# RTD_1k_Wheatstone_PGA-ADC.net
KiCad netlist of a schematic drawn in Altium Designer
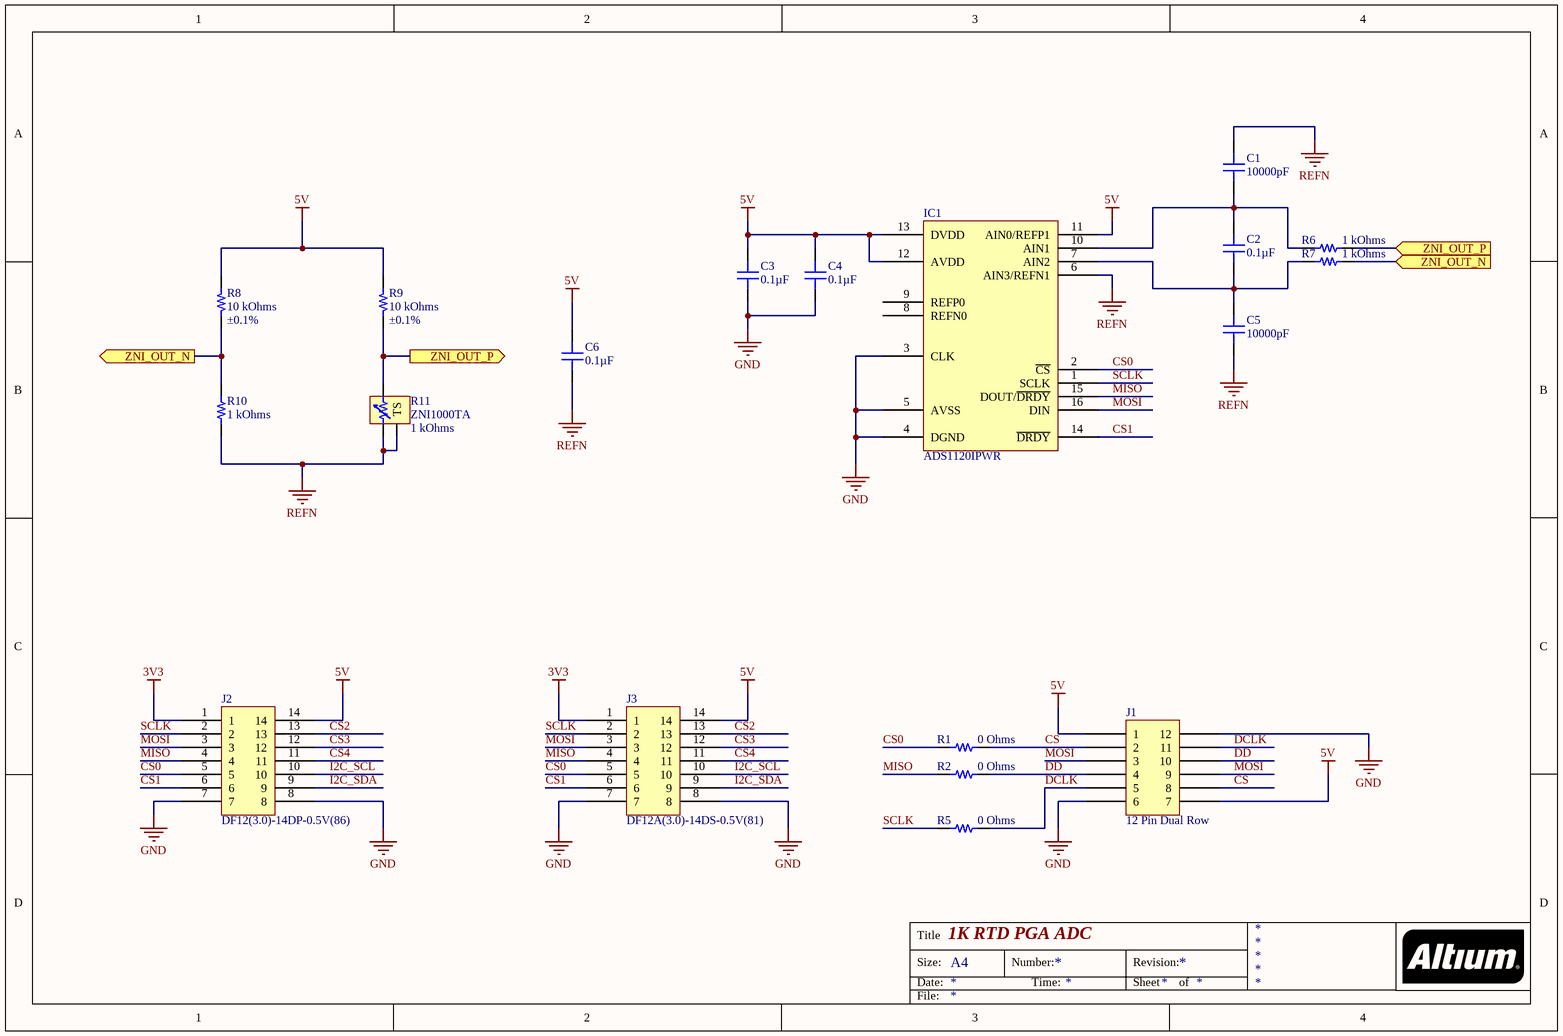
[diagram p0: RTD 1k Wheatstone PGA-ADC.SchDoc]

(export (version "E")
  (design (tool "Eeschema 10.0.6"))
  (components
    (comp (ref "C1")
      (value "10000pF")
      (footprint "CAP 0603_1608")
      (description "CAP CER 10000PF 50V X7R 0603")
      (fields (field (name "PART NUMBER") "AC0603KPX7R9BB103") (field (name "MANUFACTURER") "Yageo"))
      (libsource (lib "altiumlibrary.com") (part "Capacitor"))
    )
    (comp (ref "C2")
      (value "0.1µF")
      (footprint "CAP 0603_1608")
      (description "CAP CER 0.1UF 16V Y5V 0603")
      (fields (field (name "PART NUMBER") "CC0603ZRY5V7BB104") (field (name "MANUFACTURER") "Yageo"))
      (libsource (lib "altiumlibrary.com") (part "Capacitor"))
    )
    (comp (ref "C3")
      (value "0.1µF")
      (footprint "CAP 0603_1608")
      (description "CAP CER 0.1UF 16V Y5V 0603")
      (fields (field (name "PART NUMBER") "CC0603ZRY5V7BB104") (field (name "MANUFACTURER") "Yageo"))
      (libsource (lib "altiumlibrary.com") (part "Capacitor"))
    )
    (comp (ref "C4")
      (value "0.1µF")
      (footprint "CAP 0603_1608")
      (description "CAP CER 0.1UF 16V Y5V 0603")
      (fields (field (name "PART NUMBER") "CC0603ZRY5V7BB104") (field (name "MANUFACTURER") "Yageo"))
      (libsource (lib "altiumlibrary.com") (part "Capacitor"))
    )
    (comp (ref "C5")
      (value "10000pF")
      (footprint "CAP 0603_1608")
      (description "CAP CER 10000PF 50V X7R 0603")
      (fields (field (name "PART NUMBER") "AC0603KPX7R9BB103") (field (name "MANUFACTURER") "Yageo"))
      (libsource (lib "altiumlibrary.com") (part "Capacitor"))
    )
    (comp (ref "C6")
      (value "0.1µF")
      (footprint "CAP 0603_1608")
      (description "CAP CER 0.1UF 16V Y5V 0603")
      (fields (field (name "PART NUMBER") "CC0603ZRY5V7BB104") (field (name "MANUFACTURER") "Yageo"))
      (libsource (lib "altiumlibrary.com") (part "Capacitor"))
    )
    (comp (ref "IC1")
      (value "ADS1120IPWR")
      (footprint "TI TSSOP-16 PW")
      (description "IC ADC 16BIT SIGMA-DELTA 16TSSOP")
      (fields (field (name "MANUFACTURER") "Texas Instruments"))
      (libsource (lib "altiumlibrary.com") (part "TI ADS1120 TSSOP"))
    )
    (comp (ref "J1")
      (value "12 Pin Dual Row")
      (footprint "TE 5650118-3 Card Edge")
      (libsource (lib "CelestialUseful") (part "12 Pin Dual Row"))
    )
    (comp (ref "J2")
      (value "DF12(3.0)-14DP-0.5V(86)")
      (footprint "HIROSE DF12 3.0-14DP-0.5V 86")
      (description "CONN HDR 14POS SMD GOLD")
      (fields (field (name "MANUFACTURER") "Hirose Electric Co Ltd"))
      (libsource (lib "altiumlibrary.com") (part "14 Pin Dual Row"))
    )
    (comp (ref "J3")
      (value "DF12A(3.0)-14DS-0.5V(81)")
      (footprint "HIROSE DF12A 3.0-14DS-0.5V 81")
      (description "CONN RCPT 14POS SMD GOLD")
      (fields (field (name "MANUFACTURER") "Hirose Electric Co Ltd"))
      (libsource (lib "altiumlibrary.com") (part "14 Pin Dual Row"))
    )
    (comp (ref "R1")
      (value "0 Ohms")
      (footprint "RES 0603_1608")
      (description "RES SMD 0 OHM JUMPER 1/10W 0603")
      (fields
        (field (name "PART NUMBER") "ERJ-3GEY0R00V")
        (field (name "MANUFACTURER") "Panasonic Electronic Components")
      )
      (libsource (lib "altiumlibrary.com") (part "Resistor"))
    )
    (comp (ref "R2")
      (value "0 Ohms")
      (footprint "RES 0603_1608")
      (description "RES SMD 0 OHM JUMPER 1/10W 0603")
      (fields
        (field (name "PART NUMBER") "ERJ-3GEY0R00V")
        (field (name "MANUFACTURER") "Panasonic Electronic Components")
      )
      (libsource (lib "altiumlibrary.com") (part "Resistor"))
    )
    (comp (ref "R5")
      (value "0 Ohms")
      (footprint "RES 0603_1608")
      (description "RES SMD 0 OHM JUMPER 1/10W 0603")
      (fields
        (field (name "PART NUMBER") "ERJ-3GEY0R00V")
        (field (name "MANUFACTURER") "Panasonic Electronic Components")
      )
      (libsource (lib "altiumlibrary.com") (part "Resistor"))
    )
    (comp (ref "R6")
      (value "1 kOhms")
      (footprint "RES 0603_1608")
      (description "RES SMD 1K OHM 0.1% 1/5W 0603")
      (fields
        (field (name "PART NUMBER") "ERJ-PB3B1001V")
        (field (name "MANUFACTURER") "Panasonic Electronic Components")
      )
      (libsource (lib "altiumlibrary.com") (part "Resistor"))
    )
    (comp (ref "R7")
      (value "1 kOhms")
      (footprint "RES 0603_1608")
      (description "RES SMD 1K OHM 0.1% 1/5W 0603")
      (fields
        (field (name "PART NUMBER") "ERJ-PB3B1001V")
        (field (name "MANUFACTURER") "Panasonic Electronic Components")
      )
      (libsource (lib "altiumlibrary.com") (part "Resistor"))
    )
    (comp (ref "R8")
      (value "10 kOhms")
      (footprint "RES 0603_1608")
      (description "RES SMD 10K OHM 0.1% 1/10W 0603")
      (fields
        (field (name "PART NUMBER") "ERA-3AEB103V")
        (field (name "MANUFACTURER") "Panasonic Electronic Components")
        (field (name "TOLERANCE") "±0.1%")
      )
      (libsource (lib "altiumlibrary.com") (part "Resistor"))
    )
    (comp (ref "R9")
      (value "10 kOhms")
      (footprint "RES 0603_1608")
      (description "RES SMD 10K OHM 0.1% 1/10W 0603")
      (fields
        (field (name "PART NUMBER") "ERA-3AEB103V")
        (field (name "MANUFACTURER") "Panasonic Electronic Components")
        (field (name "TOLERANCE") "±0.1%")
      )
      (libsource (lib "altiumlibrary.com") (part "Resistor"))
    )
    (comp (ref "R10")
      (value "1 kOhms")
      (footprint "RES 0603_1608")
      (description "RES SMD 1K OHM 0.1% 1/5W 0603")
      (fields
        (field (name "PART NUMBER") "ERJ-PB3B1001V")
        (field (name "MANUFACTURER") "Panasonic Electronic Components")
      )
      (libsource (lib "altiumlibrary.com") (part "Resistor"))
    )
    (comp (ref "R11")
      (value "ZNI1000TA")
      (footprint "DIODES SOT-23-3")
      (description "SENSOR RTD 1KOHM 5% TO236-3")
      (fields (field (name "MANUFACTURER") "Diodes Incorporated") (field (name "RESISTANCE @ 0°C") "1 kOhms"))
      (libsource (lib "altiumlibrary.com") (part "DIODES INC ZNI1000"))
    )
  )
  (nets
    (net (code "1") (name "/CS") (class "Default")
      (node (ref "J1") (pin "2") (pinfunction "2_2") (pintype "passive"))
      (node (ref "J1") (pin "8") (pinfunction "8_8") (pintype "passive"))
      (node (ref "R1") (pin "2") (pinfunction "2_2") (pintype "passive"))
    )
    (net (code "2") (name "/CS0") (class "Default")
      (node (ref "IC1") (pin "2") (pinfunction "~{CS}_2") (pintype "passive"))
      (node (ref "J2") (pin "5") (pinfunction "5_5") (pintype "passive"))
      (node (ref "J3") (pin "5") (pinfunction "5_5") (pintype "passive"))
      (node (ref "R1") (pin "1") (pinfunction "1_1") (pintype "passive"))
    )
    (net (code "3") (name "/CS1") (class "Default")
      (node (ref "IC1") (pin "14") (pinfunction "~{DRDY}_14") (pintype "passive"))
      (node (ref "J2") (pin "6") (pinfunction "6_6") (pintype "passive"))
      (node (ref "J3") (pin "6") (pinfunction "6_6") (pintype "passive"))
    )
    (net (code "4") (name "/CS2") (class "Default")
      (node (ref "J2") (pin "13") (pinfunction "13_13") (pintype "passive"))
      (node (ref "J3") (pin "13") (pinfunction "13_13") (pintype "passive"))
    )
    (net (code "5") (name "/CS3") (class "Default")
      (node (ref "J2") (pin "12") (pinfunction "12_12") (pintype "passive"))
      (node (ref "J3") (pin "12") (pinfunction "12_12") (pintype "passive"))
    )
    (net (code "6") (name "/CS4") (class "Default")
      (node (ref "J2") (pin "11") (pinfunction "11_11") (pintype "passive"))
      (node (ref "J3") (pin "11") (pinfunction "11_11") (pintype "passive"))
    )
    (net (code "7") (name "/DCLK") (class "Default")
      (node (ref "J1") (pin "11") (pinfunction "11_11") (pintype "passive"))
      (node (ref "J1") (pin "5") (pinfunction "5_5") (pintype "passive"))
      (node (ref "R5") (pin "2") (pinfunction "2_2") (pintype "passive"))
    )
    (net (code "8") (name "/DD") (class "Default")
      (node (ref "J1") (pin "10") (pinfunction "10_10") (pintype "passive"))
      (node (ref "J1") (pin "4") (pinfunction "4_4") (pintype "passive"))
      (node (ref "R2") (pin "2") (pinfunction "2_2") (pintype "passive"))
    )
    (net (code "9") (name "/I2C_SCL") (class "Default")
      (node (ref "J2") (pin "10") (pinfunction "10_10") (pintype "passive"))
      (node (ref "J3") (pin "10") (pinfunction "10_10") (pintype "passive"))
    )
    (net (code "10") (name "/I2C_SDA") (class "Default")
      (node (ref "J2") (pin "9") (pinfunction "9_9") (pintype "passive"))
      (node (ref "J3") (pin "9") (pinfunction "9_9") (pintype "passive"))
    )
    (net (code "11") (name "/MISO") (class "Default")
      (node (ref "IC1") (pin "15") (pinfunction "DOUT/~{DRDY}_15") (pintype "passive"))
      (node (ref "J2") (pin "4") (pinfunction "4_4") (pintype "passive"))
      (node (ref "J3") (pin "4") (pinfunction "4_4") (pintype "passive"))
      (node (ref "R2") (pin "1") (pinfunction "1_1") (pintype "passive"))
    )
    (net (code "12") (name "/MOSI") (class "Default")
      (node (ref "IC1") (pin "16") (pinfunction "DIN_16") (pintype "passive"))
      (node (ref "J1") (pin "3") (pinfunction "3_3") (pintype "passive"))
      (node (ref "J1") (pin "9") (pinfunction "9_9") (pintype "passive"))
      (node (ref "J2") (pin "3") (pinfunction "3_3") (pintype "passive"))
      (node (ref "J3") (pin "3") (pinfunction "3_3") (pintype "passive"))
    )
    (net (code "13") (name "/SCLK") (class "Default")
      (node (ref "IC1") (pin "1") (pinfunction "SCLK_1") (pintype "passive"))
      (node (ref "J2") (pin "2") (pinfunction "2_2") (pintype "passive"))
      (node (ref "J3") (pin "2") (pinfunction "2_2") (pintype "passive"))
      (node (ref "R5") (pin "1") (pinfunction "1_1") (pintype "passive"))
    )
    (net (code "14") (name "/ZNI_OUT_N") (class "Default")
      (node (ref "R10") (pin "2") (pinfunction "2_2") (pintype "passive"))
      (node (ref "R7") (pin "1") (pinfunction "1_1") (pintype "passive"))
      (node (ref "R8") (pin "1") (pinfunction "1_1") (pintype "passive"))
    )
    (net (code "15") (name "/ZNI_OUT_P") (class "Default")
      (node (ref "R11") (pin "2") (pinfunction "2_2") (pintype "passive"))
      (node (ref "R6") (pin "1") (pinfunction "1_1") (pintype "passive"))
      (node (ref "R9") (pin "1") (pinfunction "1_1") (pintype "passive"))
    )
    (net (code "16") (name "3V3") (class "Default")
      (node (ref "J2") (pin "1") (pinfunction "1_1") (pintype "passive"))
      (node (ref "J3") (pin "1") (pinfunction "1_1") (pintype "passive"))
    )
    (net (code "17") (name "5V") (class "Default")
      (node (ref "C3") (pin "1") (pinfunction "1_1") (pintype "passive"))
      (node (ref "C4") (pin "1") (pinfunction "1_1") (pintype "passive"))
      (node (ref "C6") (pin "1") (pinfunction "1_1") (pintype "passive"))
      (node (ref "IC1") (pin "11") (pinfunction "AIN0/REFP1_11") (pintype "passive"))
      (node (ref "IC1") (pin "12") (pinfunction "AVDD_12") (pintype "passive"))
      (node (ref "IC1") (pin "13") (pinfunction "DVDD_13") (pintype "passive"))
      (node (ref "J1") (pin "1") (pinfunction "1_1") (pintype "passive"))
      (node (ref "J1") (pin "7") (pinfunction "7_7") (pintype "passive"))
      (node (ref "J2") (pin "14") (pinfunction "14_14") (pintype "passive"))
      (node (ref "J3") (pin "14") (pinfunction "14_14") (pintype "passive"))
      (node (ref "R8") (pin "2") (pinfunction "2_2") (pintype "passive"))
      (node (ref "R9") (pin "2") (pinfunction "2_2") (pintype "passive"))
    )
    (net (code "18") (name "GND") (class "Default")
      (node (ref "C3") (pin "2") (pinfunction "2_2") (pintype "passive"))
      (node (ref "C4") (pin "2") (pinfunction "2_2") (pintype "passive"))
      (node (ref "IC1") (pin "3") (pinfunction "CLK_3") (pintype "passive"))
      (node (ref "IC1") (pin "4") (pinfunction "DGND_4") (pintype "passive"))
      (node (ref "IC1") (pin "5") (pinfunction "AVSS_5") (pintype "passive"))
      (node (ref "J1") (pin "12") (pinfunction "12_12") (pintype "passive"))
      (node (ref "J1") (pin "6") (pinfunction "6_6") (pintype "passive"))
      (node (ref "J2") (pin "7") (pinfunction "7_7") (pintype "passive"))
      (node (ref "J2") (pin "8") (pinfunction "8_8") (pintype "passive"))
      (node (ref "J3") (pin "7") (pinfunction "7_7") (pintype "passive"))
      (node (ref "J3") (pin "8") (pinfunction "8_8") (pintype "passive"))
    )
    (net (code "19") (name "Net-(IC1-AIN1)") (class "Default")
      (node (ref "C1") (pin "1") (pinfunction "1_1") (pintype "passive"))
      (node (ref "C2") (pin "1") (pinfunction "1_1") (pintype "passive"))
      (node (ref "IC1") (pin "10") (pinfunction "AIN1_10") (pintype "passive"))
      (node (ref "R6") (pin "2") (pinfunction "2_2") (pintype "passive"))
    )
    (net (code "20") (name "Net-(IC1-AIN2)") (class "Default")
      (node (ref "C2") (pin "2") (pinfunction "2_2") (pintype "passive"))
      (node (ref "C5") (pin "2") (pinfunction "2_2") (pintype "passive"))
      (node (ref "IC1") (pin "7") (pinfunction "AIN2_7") (pintype "passive"))
      (node (ref "R7") (pin "2") (pinfunction "2_2") (pintype "passive"))
    )
    (net (code "21") (name "REFN") (class "Default")
      (node (ref "C1") (pin "2") (pinfunction "2_2") (pintype "passive"))
      (node (ref "C5") (pin "1") (pinfunction "1_1") (pintype "passive"))
      (node (ref "C6") (pin "2") (pinfunction "2_2") (pintype "passive"))
      (node (ref "IC1") (pin "6") (pinfunction "AIN3/REFN1_6") (pintype "passive"))
      (node (ref "R10") (pin "1") (pinfunction "1_1") (pintype "passive"))
      (node (ref "R11") (pin "1") (pinfunction "1_1") (pintype "passive"))
      (node (ref "R11") (pin "3") (pinfunction "TS_3") (pintype "passive"))
    )
    (net (code "22") (name "unconnected-(IC1-REFN0-Pad8)") (class "Default")
      (node (ref "IC1") (pin "8") (pinfunction "REFN0_8") (pintype "passive"))
    )
    (net (code "23") (name "unconnected-(IC1-REFP0-Pad9)") (class "Default")
      (node (ref "IC1") (pin "9") (pinfunction "REFP0_9") (pintype "passive"))
    )
  )
)
